# MicroSD.net
KiCad netlist of a schematic drawn in Altium Designer
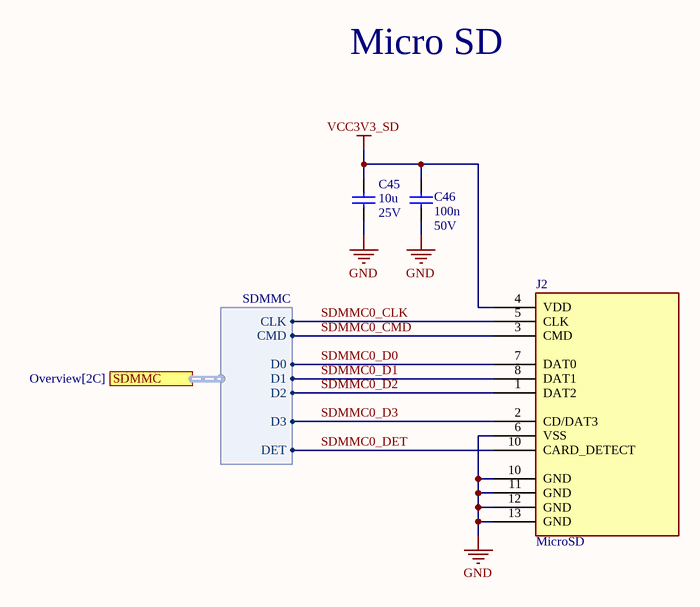
[diagram p0: MicroSD.SchDoc]

(export (version "E")
  (design (tool "Eeschema 10.0.6"))
  (components
    (comp (ref "C45")
      (value "10u")
      (description "CAP 10U 25V X5R 0603")
      (fields (field (name "VOLTAGE") "25V") (field (name "Comment") "GRM188R61E106MA73D"))
      (libsource (lib "PersonalAltiumLibrary") (part "GRM188R61E106MA73D"))
    )
    (comp (ref "C46")
      (value "100n")
      (footprint "GRM155R71H104KE14D")
      (description "CAP 100N 50V X7R 0402")
      (fields (field (name "VOLTAGE") "50V") (field (name "Comment") "GRM155R71H104KE14D"))
      (libsource (lib "PersonalAltiumLibrary") (part "GRM155R71H104KE14D"))
    )
    (comp (ref "J2") (value "MicroSD") (libsource (lib "PersonalAltiumLibrary") (part "MicroSD")))
  )
  (nets
    (net (code "2") (name "/SDMMC0_CLK") (class "Default")
      (node (ref "J2") (pin "5") (pinfunction "CLK_5") (pintype "passive"))
    )
    (net (code "3") (name "/SDMMC0_CMD") (class "Default")
      (node (ref "J2") (pin "3") (pinfunction "CMD_3") (pintype "passive"))
    )
    (net (code "4") (name "/SDMMC0_D0") (class "Default")
      (node (ref "J2") (pin "7") (pinfunction "DAT0_7") (pintype "passive"))
    )
    (net (code "5") (name "/SDMMC0_D1") (class "Default")
      (node (ref "J2") (pin "8") (pinfunction "DAT1_8") (pintype "passive"))
    )
    (net (code "6") (name "/SDMMC0_D2") (class "Default")
      (node (ref "J2") (pin "1") (pinfunction "DAT2_1") (pintype "passive"))
    )
    (net (code "7") (name "/SDMMC0_D3") (class "Default")
      (node (ref "J2") (pin "2") (pinfunction "CD/DAT3_2") (pintype "passive"))
    )
    (net (code "8") (name "/SDMMC0_DET") (class "Default")
      (node (ref "J2") (pin "10") (pinfunction "CARD_DETECT_10") (pintype "passive"))
    )
    (net (code "10") (name "GND") (class "Default")
      (node (ref "C45") (pin "2") (pinfunction "2_2") (pintype "passive"))
      (node (ref "C46") (pin "2") (pinfunction "2_2") (pintype "passive"))
      (node (ref "J2") (pin "10") (pinfunction "GND_10") (pintype "passive"))
      (node (ref "J2") (pin "11") (pinfunction "GND_11") (pintype "passive"))
      (node (ref "J2") (pin "12") (pinfunction "GND_12") (pintype "passive"))
      (node (ref "J2") (pin "13") (pinfunction "GND_13") (pintype "passive"))
      (node (ref "J2") (pin "6") (pinfunction "VSS_6") (pintype "passive"))
    )
    (net (code "11") (name "VCC3V3_SD") (class "Default")
      (node (ref "C45") (pin "1") (pinfunction "1_1") (pintype "passive"))
      (node (ref "C46") (pin "1") (pinfunction "1_1") (pintype "passive"))
      (node (ref "J2") (pin "4") (pinfunction "VDD_4") (pintype "passive"))
    )
  )
)
